# ADC.net
KiCad netlist of a schematic drawn in Altium Designer
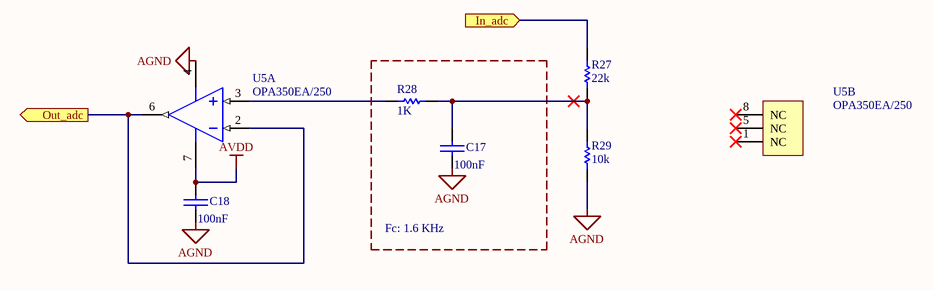
[diagram p0: ADC.SchDoc]

(export (version "E")
  (design (tool "Eeschema 10.0.6"))
  (components
    (comp (ref "C17")
      (value "100nF")
      (footprint "0603C")
      (description "Capacitor")
      (libsource (lib "MB1137") (part "CAP"))
    )
    (comp (ref "C18")
      (value "100nF")
      (footprint "0603C")
      (description "Capacitor")
      (libsource (lib "MB1137") (part "CAP"))
    )
    (comp (ref "R27")
      (value "22k")
      (footprint "0603R")
      (description "Resistor 0402 / 0603 / 0805")
      (libsource (lib "MB1137") (part "Resistor_ST"))
    )
    (comp (ref "R28")
      (value "1K")
      (footprint "0603R")
      (description "Resistor 0402 / 0603 / 0805")
      (libsource (lib "MB1137") (part "Resistor_ST"))
    )
    (comp (ref "R29")
      (value "10k")
      (footprint "0603R")
      (description "Resistor 0402 / 0603 / 0805")
      (libsource (lib "MB1137") (part "Resistor_ST"))
    )
    (comp (ref "U5")
      (value "OPA350EA/250")
      (footprint "DGK0008A_M")
      (fields (field (name "MANUFACTURER") "Texas Instruments"))
      (libsource (lib "Altium Content Vault") (part "TI-OPA-8_1"))
    )
  )
  (nets
    (net (code "1") (name "/In_adc") (class "Default")
      (node (ref "R27") (pin "2") (pinfunction "2_2") (pintype "passive"))
    )
    (net (code "2") (name "/Out_adc") (class "Default")
      (node (ref "U5") (pin "2") (pinfunction "IN-_2") (pintype "input"))
      (node (ref "U5") (pin "6") (pinfunction "OUT_6") (pintype "output"))
    )
    (net (code "3") (name "AGND") (class "Default")
      (node (ref "C17") (pin "2") (pinfunction "2_2") (pintype "passive"))
      (node (ref "C18") (pin "2") (pinfunction "2_2") (pintype "passive"))
      (node (ref "R29") (pin "1") (pinfunction "1_1") (pintype "passive"))
      (node (ref "U5") (pin "4") (pinfunction "V-_4") (pintype "power_in"))
    )
    (net (code "4") (name "AVDD") (class "Default")
      (node (ref "C18") (pin "1") (pinfunction "1_1") (pintype "passive"))
      (node (ref "U5") (pin "7") (pinfunction "V+_7") (pintype "power_in"))
    )
    (net (code "5") (name "Net-(C17-Pad1)") (class "Default")
      (node (ref "C17") (pin "1") (pinfunction "1_1") (pintype "passive"))
      (node (ref "R27") (pin "1") (pinfunction "1_1") (pintype "passive"))
      (node (ref "R28") (pin "1") (pinfunction "1_1") (pintype "passive"))
      (node (ref "R29") (pin "2") (pinfunction "2_2") (pintype "passive"))
    )
    (net (code "6") (name "Net-(U5A-IN+)") (class "Default")
      (node (ref "R28") (pin "2") (pinfunction "2_2") (pintype "passive"))
      (node (ref "U5") (pin "3") (pinfunction "IN+_3") (pintype "input"))
    )
    (net (code "7") (name "unconnected-(U5B-NC-Pad1)") (class "Default")
      (node (ref "U5") (pin "1") (pinfunction "NC_1") (pintype "passive+no_connect"))
    )
    (net (code "8") (name "unconnected-(U5B-NC-Pad5)") (class "Default")
      (node (ref "U5") (pin "5") (pinfunction "NC_5") (pintype "passive+no_connect"))
    )
    (net (code "9") (name "unconnected-(U5B-NC-Pad8)") (class "Default")
      (node (ref "U5") (pin "8") (pinfunction "NC_8") (pintype "passive+no_connect"))
    )
  )
)
